# noise_lev_rev1.net
KiCad netlist of a schematic drawn in EAGLE
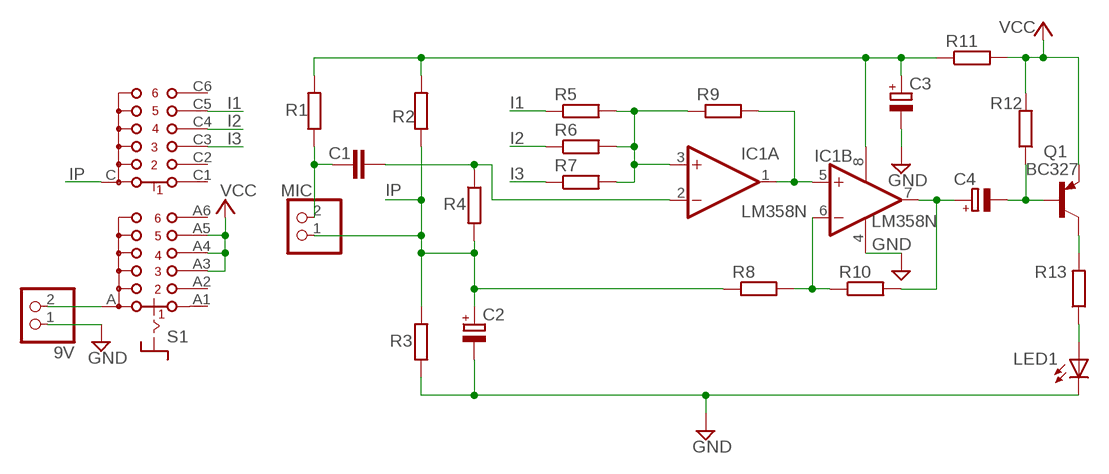
[diagram p0: schematic, sheet 1]

(export (version "E")
  (design (tool "Eeschema 10.0.6"))
  (components
    (comp (ref "9V")
      (value "PINHD-1X2")
      (footprint "eagle-import:1X02")
      (libsource (lib "eagle-import") (part "PINHD-1X2"))
    )
    (comp (ref "C1")
      (value "C-EU025-025X050")
      (footprint "eagle-import:C025-025X050")
      (libsource (lib "eagle-import") (part "C-EU025-025X050"))
    )
    (comp (ref "C2")
      (value "CPOL-EUE2.5-5")
      (footprint "eagle-import:E2,5-5")
      (libsource (lib "eagle-import") (part "CPOL-EUE2.5-5"))
    )
    (comp (ref "C3")
      (value "CPOL-EUE5-10.5")
      (footprint "eagle-import:E5-10,5")
      (libsource (lib "eagle-import") (part "CPOL-EUE5-10.5"))
    )
    (comp (ref "C4")
      (value "CPOL-EUE2.5-5")
      (footprint "eagle-import:E2,5-5")
      (libsource (lib "eagle-import") (part "CPOL-EUE2.5-5"))
    )
    (comp (ref "IC1")
      (value "LM358N")
      (footprint "eagle-import:DIL08")
      (libsource (lib "eagle-import") (part "LM358N"))
    )
    (comp (ref "LED1")
      (value "LED5MM")
      (footprint "eagle-import:LED5MM")
      (libsource (lib "eagle-import") (part "LED5MM"))
    )
    (comp (ref "MIC")
      (value "PINHD-1X2")
      (footprint "eagle-import:1X02")
      (libsource (lib "eagle-import") (part "PINHD-1X2"))
    )
    (comp (ref "Q1")
      (value "BC327")
      (footprint "eagle-import:TO92-EBC")
      (libsource (lib "eagle-import") (part "BC327"))
    )
    (comp (ref "R1")
      (value "R-EU_0207/10")
      (footprint "eagle-import:0207_10")
      (libsource (lib "eagle-import") (part "R-EU_0207/10"))
    )
    (comp (ref "R2")
      (value "R-EU_0207/10")
      (footprint "eagle-import:0207_10")
      (libsource (lib "eagle-import") (part "R-EU_0207/10"))
    )
    (comp (ref "R3")
      (value "R-EU_0207/10")
      (footprint "eagle-import:0207_10")
      (libsource (lib "eagle-import") (part "R-EU_0207/10"))
    )
    (comp (ref "R4")
      (value "R-EU_0207/10")
      (footprint "eagle-import:0207_10")
      (libsource (lib "eagle-import") (part "R-EU_0207/10"))
    )
    (comp (ref "R5")
      (value "R-EU_0207/10")
      (footprint "eagle-import:0207_10")
      (libsource (lib "eagle-import") (part "R-EU_0207/10"))
    )
    (comp (ref "R6")
      (value "R-EU_0207/10")
      (footprint "eagle-import:0207_10")
      (libsource (lib "eagle-import") (part "R-EU_0207/10"))
    )
    (comp (ref "R7")
      (value "R-EU_0207/10")
      (footprint "eagle-import:0207_10")
      (libsource (lib "eagle-import") (part "R-EU_0207/10"))
    )
    (comp (ref "R8")
      (value "R-EU_0207/10")
      (footprint "eagle-import:0207_10")
      (libsource (lib "eagle-import") (part "R-EU_0207/10"))
    )
    (comp (ref "R9")
      (value "R-EU_0207/10")
      (footprint "eagle-import:0207_10")
      (libsource (lib "eagle-import") (part "R-EU_0207/10"))
    )
    (comp (ref "R10")
      (value "R-EU_0207/10")
      (footprint "eagle-import:0207_10")
      (libsource (lib "eagle-import") (part "R-EU_0207/10"))
    )
    (comp (ref "R11")
      (value "R-EU_0207/10")
      (footprint "eagle-import:0207_10")
      (libsource (lib "eagle-import") (part "R-EU_0207/10"))
    )
    (comp (ref "R12")
      (value "R-EU_0207/10")
      (footprint "eagle-import:0207_10")
      (libsource (lib "eagle-import") (part "R-EU_0207/10"))
    )
    (comp (ref "R13")
      (value "R-EU_0207/10")
      (footprint "eagle-import:0207_10")
      (libsource (lib "eagle-import") (part "R-EU_0207/10"))
    )
    (comp (ref "S1")
      (value "CK102X06")
      (footprint "eagle-import:CK102X06")
      (libsource (lib "eagle-import") (part "CK102X06"))
    )
  )
  (nets
    (net (code "1") (name "/I1") (class "Default")
      (node (ref "R5") (pin "1") (pinfunction "1_1") (pintype "passive"))
      (node (ref "S1") (pin "C5") (pinfunction "C5_C5") (pintype "passive"))
    )
    (net (code "2") (name "/I2") (class "Default")
      (node (ref "R6") (pin "1") (pinfunction "1_1") (pintype "passive"))
      (node (ref "S1") (pin "C4") (pinfunction "C4_C4") (pintype "passive"))
    )
    (net (code "3") (name "/I3") (class "Default")
      (node (ref "R7") (pin "1") (pinfunction "1_1") (pintype "passive"))
      (node (ref "S1") (pin "C3") (pinfunction "C3_C3") (pintype "passive"))
    )
    (net (code "4") (name "/IP") (class "Default")
      (node (ref "C2") (pin "+") (pinfunction "+_+") (pintype "passive"))
      (node (ref "MIC") (pin "1") (pinfunction "1_1") (pintype "passive"))
      (node (ref "R2") (pin "1") (pinfunction "1_1") (pintype "passive"))
      (node (ref "R3") (pin "2") (pinfunction "2_2") (pintype "passive"))
      (node (ref "R4") (pin "2") (pinfunction "2_2") (pintype "passive"))
      (node (ref "R8") (pin "1") (pinfunction "1_1") (pintype "passive"))
      (node (ref "S1") (pin "C") (pinfunction "C_C") (pintype "passive"))
    )
    (net (code "5") (name "GND") (class "Default")
      (node (ref "9V") (pin "1") (pinfunction "1_1") (pintype "passive"))
      (node (ref "C2") (pin "-") (pinfunction "-_-") (pintype "passive"))
      (node (ref "C3") (pin "-") (pinfunction "-_-") (pintype "passive"))
      (node (ref "IC1") (pin "4") (pinfunction "V-_4") (pintype "power_in"))
      (node (ref "LED1") (pin "K") (pinfunction "C_K") (pintype "passive"))
      (node (ref "R3") (pin "1") (pinfunction "1_1") (pintype "passive"))
    )
    (net (code "6") (name "Net-(9V-Pad2)") (class "Default")
      (node (ref "9V") (pin "2") (pinfunction "2_2") (pintype "passive"))
      (node (ref "S1") (pin "A") (pinfunction "A_A") (pintype "passive"))
    )
    (net (code "7") (name "Net-(C1-Pad1)") (class "Default")
      (node (ref "C1") (pin "1") (pinfunction "1_1") (pintype "passive"))
      (node (ref "MIC") (pin "2") (pinfunction "2_2") (pintype "passive"))
      (node (ref "R1") (pin "1") (pinfunction "1_1") (pintype "passive"))
    )
    (net (code "8") (name "Net-(C4-Pad-)") (class "Default")
      (node (ref "C4") (pin "-") (pinfunction "-_-") (pintype "passive"))
      (node (ref "Q1") (pin "B") (pinfunction "B_B") (pintype "passive"))
      (node (ref "R12") (pin "1") (pinfunction "1_1") (pintype "passive"))
    )
    (net (code "9") (name "Net-(IC1A-+IN)") (class "Default")
      (node (ref "IC1") (pin "3") (pinfunction "+IN_3") (pintype "input"))
      (node (ref "R5") (pin "2") (pinfunction "2_2") (pintype "passive"))
      (node (ref "R6") (pin "2") (pinfunction "2_2") (pintype "passive"))
      (node (ref "R7") (pin "2") (pinfunction "2_2") (pintype "passive"))
      (node (ref "R9") (pin "1") (pinfunction "1_1") (pintype "passive"))
    )
    (net (code "10") (name "Net-(IC1A--IN)") (class "Default")
      (node (ref "C1") (pin "2") (pinfunction "2_2") (pintype "passive"))
      (node (ref "IC1") (pin "2") (pinfunction "-IN_2") (pintype "input"))
      (node (ref "R4") (pin "1") (pinfunction "1_1") (pintype "passive"))
    )
    (net (code "11") (name "Net-(IC1A-OUT)") (class "Default")
      (node (ref "IC1") (pin "1") (pinfunction "OUT_1") (pintype "output"))
      (node (ref "IC1") (pin "5") (pinfunction "+IN_5") (pintype "input"))
      (node (ref "R9") (pin "2") (pinfunction "2_2") (pintype "passive"))
    )
    (net (code "12") (name "Net-(IC1B--IN)") (class "Default")
      (node (ref "IC1") (pin "6") (pinfunction "-IN_6") (pintype "input"))
      (node (ref "R10") (pin "1") (pinfunction "1_1") (pintype "passive"))
      (node (ref "R8") (pin "2") (pinfunction "2_2") (pintype "passive"))
    )
    (net (code "13") (name "Net-(IC1B-OUT)") (class "Default")
      (node (ref "C4") (pin "+") (pinfunction "+_+") (pintype "passive"))
      (node (ref "IC1") (pin "7") (pinfunction "OUT_7") (pintype "output"))
      (node (ref "R10") (pin "2") (pinfunction "2_2") (pintype "passive"))
    )
    (net (code "14") (name "Net-(IC1C-V+)") (class "Default")
      (node (ref "C3") (pin "+") (pinfunction "+_+") (pintype "passive"))
      (node (ref "IC1") (pin "8") (pinfunction "V+_8") (pintype "power_in"))
      (node (ref "R1") (pin "2") (pinfunction "2_2") (pintype "passive"))
      (node (ref "R11") (pin "1") (pinfunction "1_1") (pintype "passive"))
      (node (ref "R2") (pin "2") (pinfunction "2_2") (pintype "passive"))
    )
    (net (code "15") (name "Net-(LED1-PadA)") (class "Default")
      (node (ref "LED1") (pin "A") (pinfunction "A_A") (pintype "passive"))
      (node (ref "R13") (pin "1") (pinfunction "1_1") (pintype "passive"))
    )
    (net (code "16") (name "Net-(Q1-PadC)") (class "Default")
      (node (ref "Q1") (pin "C") (pinfunction "C_C") (pintype "passive"))
      (node (ref "R13") (pin "2") (pinfunction "2_2") (pintype "passive"))
    )
    (net (code "17") (name "VCC") (class "Default")
      (node (ref "Q1") (pin "E") (pinfunction "E_E") (pintype "passive"))
      (node (ref "R11") (pin "2") (pinfunction "2_2") (pintype "passive"))
      (node (ref "R12") (pin "2") (pinfunction "2_2") (pintype "passive"))
      (node (ref "S1") (pin "A3") (pinfunction "A3_A3") (pintype "passive"))
      (node (ref "S1") (pin "A4") (pinfunction "A4_A4") (pintype "passive"))
      (node (ref "S1") (pin "A5") (pinfunction "A5_A5") (pintype "passive"))
    )
    (net (code "18") (name "unconnected-(S1-PadA1)") (class "Default")
      (node (ref "S1") (pin "A1") (pinfunction "A1_A1") (pintype "passive"))
    )
    (net (code "19") (name "unconnected-(S1-PadA2)") (class "Default")
      (node (ref "S1") (pin "A2") (pinfunction "A2_A2") (pintype "passive"))
    )
    (net (code "20") (name "unconnected-(S1-PadA6)") (class "Default")
      (node (ref "S1") (pin "A6") (pinfunction "A6_A6") (pintype "passive"))
    )
    (net (code "21") (name "unconnected-(S1-PadC1)") (class "Default")
      (node (ref "S1") (pin "C1") (pinfunction "C1_C1") (pintype "passive"))
    )
    (net (code "22") (name "unconnected-(S1-PadC2)") (class "Default")
      (node (ref "S1") (pin "C2") (pinfunction "C2_C2") (pintype "passive"))
    )
    (net (code "23") (name "unconnected-(S1-PadC6)") (class "Default")
      (node (ref "S1") (pin "C6") (pinfunction "C6_C6") (pintype "passive"))
    )
  )
)
